# logic384.net
KiCad netlist of a schematic drawn in EAGLE
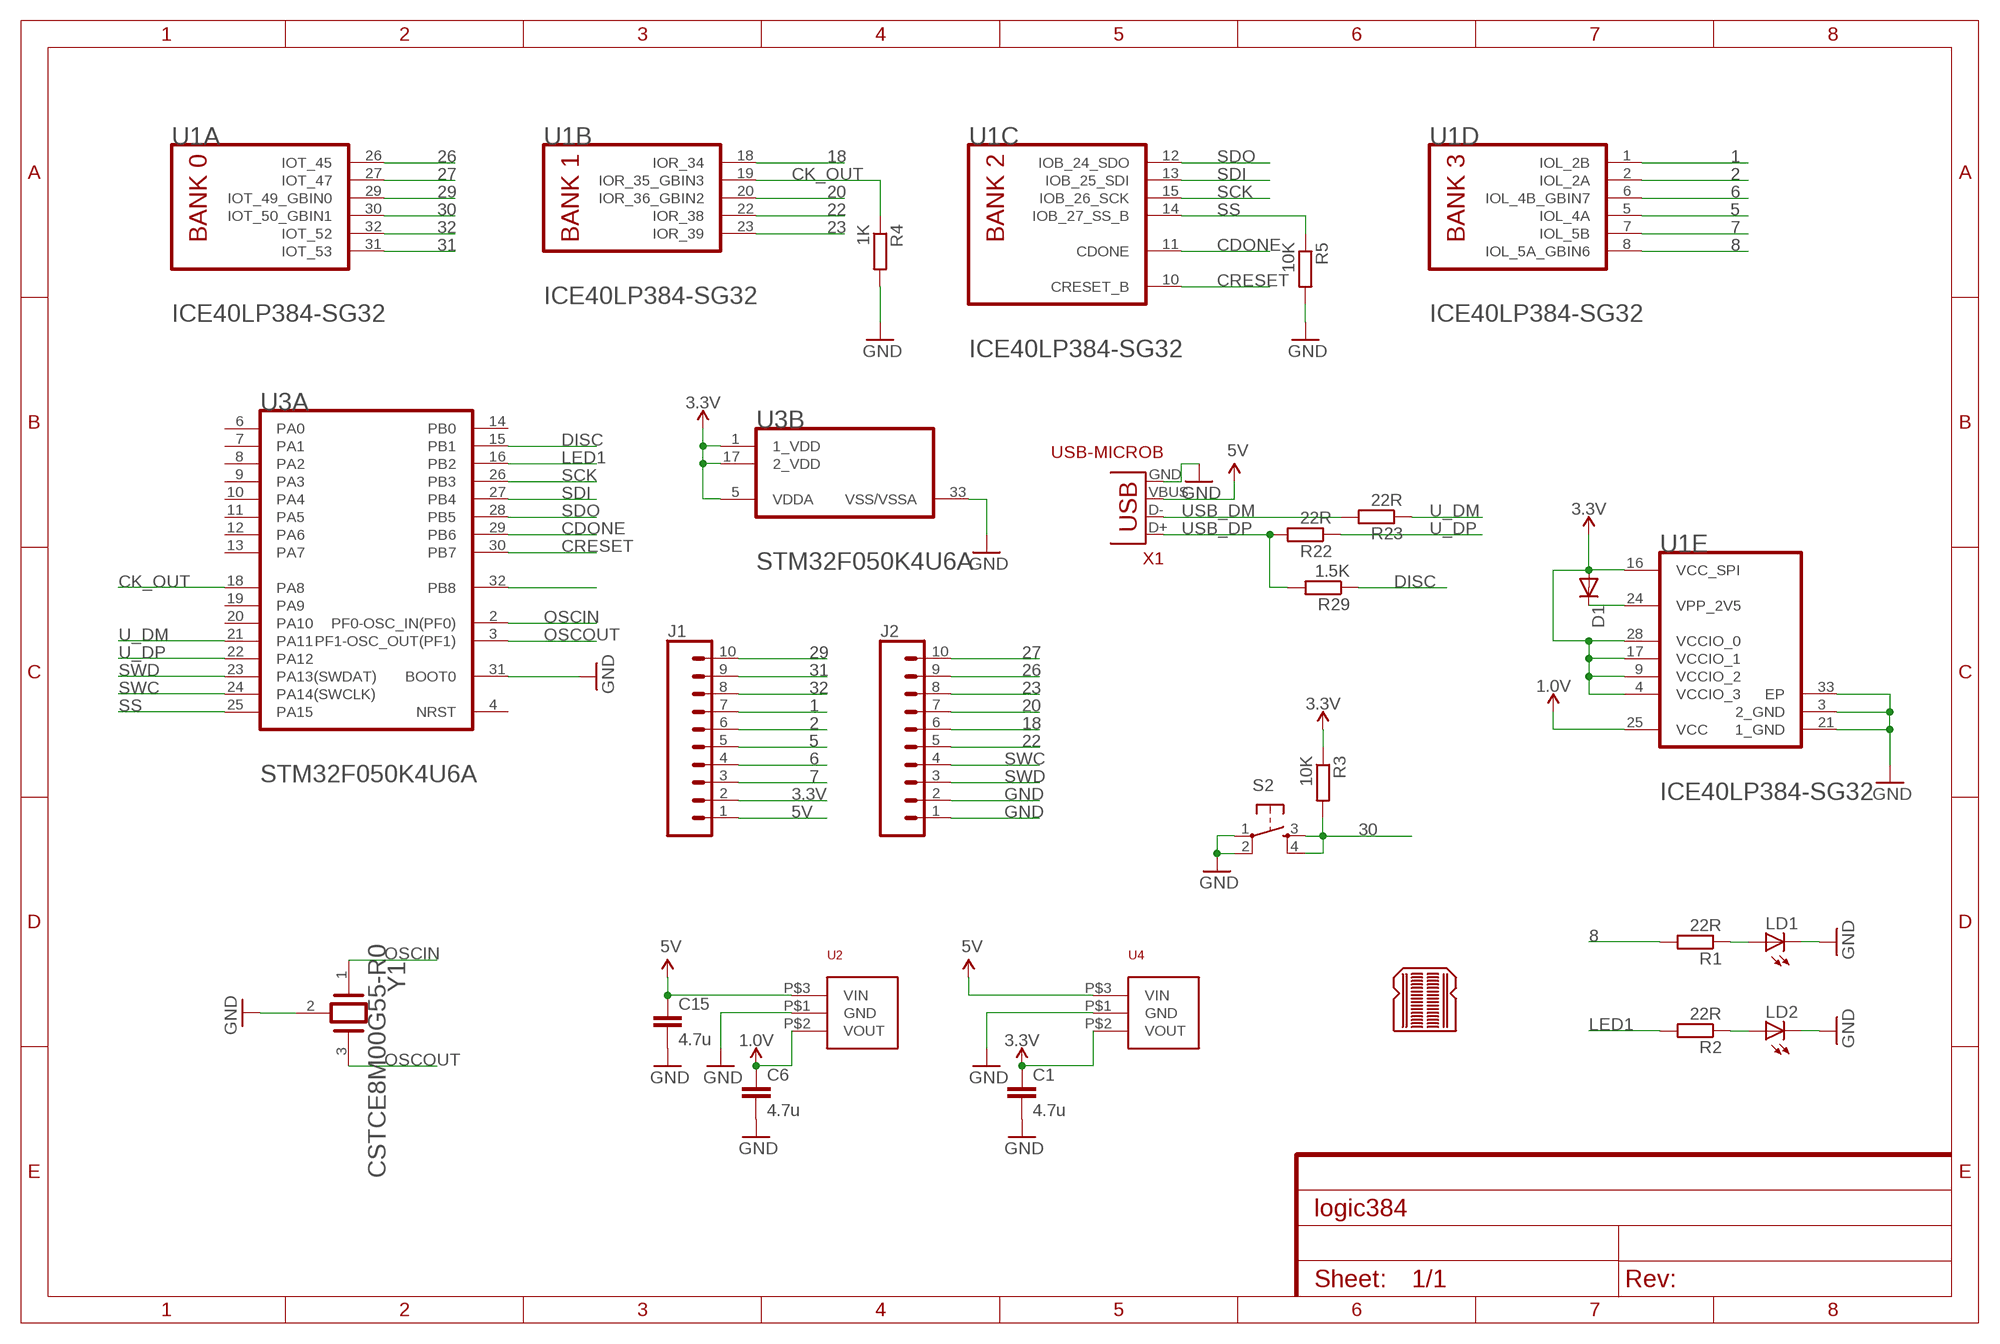
[diagram p0: schematic, sheet 1]

(export (version "E")
  (design (tool "Eeschema 10.0.6"))
  (components
    (comp (ref "C1")
      (value "4.7u")
      (footprint "eagle-import:0402-CAP")
      (libsource (lib "eagle-import") (part "CAP0402-CAP"))
    )
    (comp (ref "C6")
      (value "4.7u")
      (footprint "eagle-import:0402-CAP")
      (libsource (lib "eagle-import") (part "CAP0402-CAP"))
    )
    (comp (ref "C15")
      (value "4.7u")
      (footprint "eagle-import:0402-CAP")
      (libsource (lib "eagle-import") (part "CAP0402-CAP"))
    )
    (comp (ref "D1")
      (value "DIODE-SOD523")
      (footprint "eagle-import:SOD523")
      (libsource (lib "eagle-import") (part "DIODE-SOD523"))
    )
    (comp (ref "J1")
      (value "CONN_10NO_SILK_PTH_FEMALE")
      (footprint "eagle-import:1X10_NO_SILK")
      (libsource (lib "eagle-import") (part "CONN_10NO_SILK_PTH_FEMALE"))
    )
    (comp (ref "J2")
      (value "CONN_10NO_SILK_PTH_FEMALE")
      (footprint "eagle-import:1X10_NO_SILK")
      (libsource (lib "eagle-import") (part "CONN_10NO_SILK_PTH_FEMALE"))
    )
    (comp (ref "LD1")
      (value "LED0603")
      (footprint "eagle-import:LED-0603")
      (libsource (lib "eagle-import") (part "LED0603"))
    )
    (comp (ref "LD2")
      (value "LED0603")
      (footprint "eagle-import:LED-0603")
      (libsource (lib "eagle-import") (part "LED0603"))
    )
    (comp (ref "LOGO1")
      (value "BREADBOARD_PATTERN")
      (footprint "eagle-import:BREADBOARD_SPACING")
      (libsource (lib "eagle-import") (part "BREADBOARD_PATTERN"))
    )
    (comp (ref "R1")
      (value "22R")
      (footprint "eagle-import:R0402")
      (libsource (lib "eagle-import") (part "R-EU_R0402"))
    )
    (comp (ref "R2")
      (value "22R")
      (footprint "eagle-import:R0402")
      (libsource (lib "eagle-import") (part "R-EU_R0402"))
    )
    (comp (ref "R3")
      (value "10K")
      (footprint "eagle-import:R0402")
      (libsource (lib "eagle-import") (part "R-EU_R0402"))
    )
    (comp (ref "R4")
      (value "1K")
      (footprint "eagle-import:R0402")
      (libsource (lib "eagle-import") (part "R-EU_R0402"))
    )
    (comp (ref "R5")
      (value "10K")
      (footprint "eagle-import:R0402")
      (libsource (lib "eagle-import") (part "R-EU_R0402"))
    )
    (comp (ref "R22")
      (value "22R")
      (footprint "eagle-import:R0402")
      (libsource (lib "eagle-import") (part "R-EU_R0402"))
    )
    (comp (ref "R23")
      (value "22R")
      (footprint "eagle-import:R0402")
      (libsource (lib "eagle-import") (part "R-EU_R0402"))
    )
    (comp (ref "R29")
      (value "1.5K")
      (footprint "eagle-import:R0402")
      (libsource (lib "eagle-import") (part "R-EU_R0402"))
    )
    (comp (ref "S2")
      (value "TAC_SWITCHSMD")
      (footprint "eagle-import:TACTILE_SWITCH_SMD")
      (libsource (lib "eagle-import") (part "TAC_SWITCHSMD"))
    )
    (comp (ref "U1")
      (value "LATTICE_SEMICONDUCTOR_ICE40LP384-SG32LATTICE_SEMICONDUCTOR_ICE40LP384-SG32_0_1")
      (footprint "eagle-import:LATTICE_SEMICONDUCTOR_ICE40LP384-SG32_1")
      (fields (field (name "MF") "Lattice Semiconductor") (field (name "MPN") "ICE40LP384-SG32"))
      (libsource (lib "eagle-import") (part "LATTICE_SEMICONDUCTOR_ICE40LP384-SG32LATTICE_SEMICONDUCTOR_ICE40LP384-SG32_0_1"))
    )
    (comp (ref "U2")
      (value "MCP1703SOT-3.3V")
      (footprint "eagle-import:SOT-23A")
      (libsource (lib "eagle-import") (part "MCP1703SOT"))
    )
    (comp (ref "U3")
      (value "STMICROELECTRONICS_STM32F050K4U6ASTMICROELECTRONICS_STM32F050K4U6A_0_1")
      (footprint "eagle-import:STMICROELECTRONICS_STM32F050K4U6A_1")
      (fields (field (name "MF") "STMicroelectronics") (field (name "MPN") "STM32F050K4U6A"))
      (libsource (lib "eagle-import") (part "STMICROELECTRONICS_STM32F050K4U6ASTMICROELECTRONICS_STM32F050K4U6A_0_1"))
    )
    (comp (ref "U4")
      (value "MCP1703SOT-3.3V")
      (footprint "eagle-import:SOT-23A")
      (libsource (lib "eagle-import") (part "MCP1703SOT"))
    )
    (comp (ref "X1")
      (value "USB-MICROB")
      (footprint "eagle-import:USB-MICROB")
      (libsource (lib "eagle-import") (part "USB-MICROB"))
    )
    (comp (ref "Y1")
      (value "MURATA_CSTCE8M00G55-R0MURATA_CSTCE8M00G55-R0_0_0")
      (footprint "eagle-import:MURATA_CSTCE8M00G55-R0_0")
      (fields
        (field (name "DIGIKEY_PART_NUMBER") "490-1195-1-ND")
        (field (name "MF") "Murata")
        (field (name "MOUSER_PART_NUMBER") "81-CSTCE8M00G55-R0")
      )
      (libsource (lib "eagle-import") (part "MURATA_CSTCE8M00G55-R0MURATA_CSTCE8M00G55-R0_0_0"))
    )
  )
  (nets
    (net (code "1") (name "/1") (class "Default")
      (node (ref "J1") (pin "7") (pinfunction "7_7") (pintype "passive"))
      (node (ref "U1") (pin "1") (pinfunction "IOL_2B_1") (pintype "bidirectional"))
    )
    (net (code "2") (name "/2") (class "Default")
      (node (ref "J1") (pin "6") (pinfunction "6_6") (pintype "passive"))
      (node (ref "U1") (pin "2") (pinfunction "IOL_2A_2") (pintype "bidirectional"))
    )
    (net (code "3") (name "/5") (class "Default")
      (node (ref "J1") (pin "5") (pinfunction "5_5") (pintype "passive"))
      (node (ref "U1") (pin "5") (pinfunction "IOL_4A_5") (pintype "bidirectional"))
    )
    (net (code "4") (name "/6") (class "Default")
      (node (ref "J1") (pin "4") (pinfunction "4_4") (pintype "passive"))
      (node (ref "U1") (pin "6") (pinfunction "IOL_4B_GBIN7_6") (pintype "bidirectional"))
    )
    (net (code "5") (name "/7") (class "Default")
      (node (ref "J1") (pin "3") (pinfunction "3_3") (pintype "passive"))
      (node (ref "U1") (pin "7") (pinfunction "IOL_5B_7") (pintype "bidirectional"))
    )
    (net (code "6") (name "/8") (class "Default")
      (node (ref "R1") (pin "2") (pinfunction "2_2") (pintype "passive"))
      (node (ref "U1") (pin "8") (pinfunction "IOL_5A_GBIN6_8") (pintype "bidirectional"))
    )
    (net (code "7") (name "/18") (class "Default")
      (node (ref "J2") (pin "6") (pinfunction "6_6") (pintype "passive"))
      (node (ref "U1") (pin "18") (pinfunction "IOR_34_18") (pintype "bidirectional"))
    )
    (net (code "8") (name "/20") (class "Default")
      (node (ref "J2") (pin "7") (pinfunction "7_7") (pintype "passive"))
      (node (ref "U1") (pin "20") (pinfunction "IOR_36_GBIN2_20") (pintype "bidirectional"))
    )
    (net (code "9") (name "/22") (class "Default")
      (node (ref "J2") (pin "5") (pinfunction "5_5") (pintype "passive"))
      (node (ref "U1") (pin "22") (pinfunction "IOR_38_22") (pintype "bidirectional"))
    )
    (net (code "10") (name "/23") (class "Default")
      (node (ref "J2") (pin "8") (pinfunction "8_8") (pintype "passive"))
      (node (ref "U1") (pin "23") (pinfunction "IOR_39_23") (pintype "bidirectional"))
    )
    (net (code "11") (name "/26") (class "Default")
      (node (ref "J2") (pin "9") (pinfunction "9_9") (pintype "passive"))
      (node (ref "U1") (pin "26") (pinfunction "IOT_45_26") (pintype "bidirectional"))
    )
    (net (code "12") (name "/27") (class "Default")
      (node (ref "J2") (pin "10") (pinfunction "10_10") (pintype "passive"))
      (node (ref "U1") (pin "27") (pinfunction "IOT_47_27") (pintype "bidirectional"))
    )
    (net (code "13") (name "/29") (class "Default")
      (node (ref "J1") (pin "10") (pinfunction "10_10") (pintype "passive"))
      (node (ref "U1") (pin "29") (pinfunction "IOT_49_GBIN0_29") (pintype "bidirectional"))
    )
    (net (code "14") (name "/30") (class "Default")
      (node (ref "R3") (pin "2") (pinfunction "2_2") (pintype "passive"))
      (node (ref "S2") (pin "3") (pinfunction "3_3") (pintype "passive"))
      (node (ref "S2") (pin "4") (pinfunction "4_4") (pintype "passive"))
      (node (ref "U1") (pin "30") (pinfunction "IOT_50_GBIN1_30") (pintype "bidirectional"))
    )
    (net (code "15") (name "/31") (class "Default")
      (node (ref "J1") (pin "9") (pinfunction "9_9") (pintype "passive"))
      (node (ref "U1") (pin "31") (pinfunction "IOT_53_31") (pintype "bidirectional"))
    )
    (net (code "16") (name "/32") (class "Default")
      (node (ref "J1") (pin "8") (pinfunction "8_8") (pintype "passive"))
      (node (ref "U1") (pin "32") (pinfunction "IOT_52_32") (pintype "bidirectional"))
    )
    (net (code "17") (name "/CDONE") (class "Default")
      (node (ref "U1") (pin "11") (pinfunction "CDONE_11") (pintype "bidirectional"))
      (node (ref "U3") (pin "29") (pinfunction "PB6_29") (pintype "bidirectional"))
    )
    (net (code "18") (name "/CK_OUT") (class "Default")
      (node (ref "R4") (pin "1") (pinfunction "1_1") (pintype "passive"))
      (node (ref "U1") (pin "19") (pinfunction "IOR_35_GBIN3_19") (pintype "bidirectional"))
      (node (ref "U3") (pin "18") (pinfunction "PA8_18") (pintype "bidirectional"))
    )
    (net (code "19") (name "/CRESET") (class "Default")
      (node (ref "U1") (pin "10") (pinfunction "CRESET_B_10") (pintype "input"))
      (node (ref "U3") (pin "30") (pinfunction "PB7_30") (pintype "bidirectional"))
    )
    (net (code "20") (name "/DISC") (class "Default")
      (node (ref "R29") (pin "1") (pinfunction "1_1") (pintype "passive"))
      (node (ref "U3") (pin "15") (pinfunction "PB1_15") (pintype "bidirectional"))
    )
    (net (code "21") (name "/LED1") (class "Default")
      (node (ref "R2") (pin "2") (pinfunction "2_2") (pintype "passive"))
      (node (ref "U3") (pin "16") (pinfunction "PB2_16") (pintype "bidirectional"))
    )
    (net (code "22") (name "/OSCIN") (class "Default")
      (node (ref "U3") (pin "2") (pinfunction "PF0-OSC_IN(PF0)_2") (pintype "bidirectional"))
      (node (ref "Y1") (pin "1") (pinfunction "1_1") (pintype "bidirectional"))
    )
    (net (code "23") (name "/OSCOUT") (class "Default")
      (node (ref "U3") (pin "3") (pinfunction "PF1-OSC_OUT(PF1)_3") (pintype "bidirectional"))
      (node (ref "Y1") (pin "3") (pinfunction "3_3") (pintype "bidirectional"))
    )
    (net (code "24") (name "/SCK") (class "Default")
      (node (ref "U1") (pin "15") (pinfunction "IOB_26_SCK_15") (pintype "bidirectional"))
      (node (ref "U3") (pin "26") (pinfunction "PB3_26") (pintype "bidirectional"))
    )
    (net (code "25") (name "/SDI") (class "Default")
      (node (ref "U1") (pin "13") (pinfunction "IOB_25_SDI_13") (pintype "bidirectional"))
      (node (ref "U3") (pin "27") (pinfunction "PB4_27") (pintype "bidirectional"))
    )
    (net (code "26") (name "/SDO") (class "Default")
      (node (ref "U1") (pin "12") (pinfunction "IOB_24_SDO_12") (pintype "bidirectional"))
      (node (ref "U3") (pin "28") (pinfunction "PB5_28") (pintype "bidirectional"))
    )
    (net (code "27") (name "/SS") (class "Default")
      (node (ref "R5") (pin "1") (pinfunction "1_1") (pintype "passive"))
      (node (ref "U1") (pin "14") (pinfunction "IOB_27_SS_B_14") (pintype "bidirectional"))
      (node (ref "U3") (pin "25") (pinfunction "PA15_25") (pintype "bidirectional"))
    )
    (net (code "28") (name "/SWC") (class "Default")
      (node (ref "J2") (pin "4") (pinfunction "4_4") (pintype "passive"))
      (node (ref "U3") (pin "24") (pinfunction "PA14(SWCLK)_24") (pintype "bidirectional"))
    )
    (net (code "29") (name "/SWD") (class "Default")
      (node (ref "J2") (pin "3") (pinfunction "3_3") (pintype "passive"))
      (node (ref "U3") (pin "23") (pinfunction "PA13(SWDAT)_23") (pintype "bidirectional"))
    )
    (net (code "30") (name "/USB_DM") (class "Default")
      (node (ref "R23") (pin "2") (pinfunction "2_2") (pintype "passive"))
      (node (ref "X1") (pin "D-") (pinfunction "D-_D-") (pintype "bidirectional"))
    )
    (net (code "31") (name "/USB_DP") (class "Default")
      (node (ref "R22") (pin "2") (pinfunction "2_2") (pintype "passive"))
      (node (ref "R29") (pin "2") (pinfunction "2_2") (pintype "passive"))
      (node (ref "X1") (pin "D+") (pinfunction "D+_D+") (pintype "bidirectional"))
    )
    (net (code "32") (name "/U_DM") (class "Default")
      (node (ref "R23") (pin "1") (pinfunction "1_1") (pintype "passive"))
      (node (ref "U3") (pin "21") (pinfunction "PA11_21") (pintype "bidirectional"))
    )
    (net (code "33") (name "/U_DP") (class "Default")
      (node (ref "R22") (pin "1") (pinfunction "1_1") (pintype "passive"))
      (node (ref "U3") (pin "22") (pinfunction "PA12_22") (pintype "bidirectional"))
    )
    (net (code "34") (name "1.0V") (class "Default")
      (node (ref "C6") (pin "1") (pinfunction "1_1") (pintype "passive"))
      (node (ref "U1") (pin "25") (pinfunction "VCC_25") (pintype "power_in"))
      (node (ref "U2") (pin "P$2") (pinfunction "VOUT_P$2") (pintype "bidirectional"))
    )
    (net (code "35") (name "3.3V") (class "Default")
      (node (ref "C1") (pin "1") (pinfunction "1_1") (pintype "passive"))
      (node (ref "D1") (pin "A") (pinfunction "A_A") (pintype "passive"))
      (node (ref "J1") (pin "2") (pinfunction "2_2") (pintype "passive"))
      (node (ref "R3") (pin "1") (pinfunction "1_1") (pintype "passive"))
      (node (ref "U1") (pin "16") (pinfunction "VCC_SPI_16") (pintype "power_in"))
      (node (ref "U1") (pin "17") (pinfunction "VCCIO_1_17") (pintype "power_in"))
      (node (ref "U1") (pin "28") (pinfunction "VCCIO_0_28") (pintype "power_in"))
      (node (ref "U1") (pin "4") (pinfunction "VCCIO_3_4") (pintype "power_in"))
      (node (ref "U1") (pin "9") (pinfunction "VCCIO_2_9") (pintype "power_in"))
      (node (ref "U3") (pin "1") (pinfunction "1_VDD_1") (pintype "power_in"))
      (node (ref "U3") (pin "17") (pinfunction "2_VDD_17") (pintype "power_in"))
      (node (ref "U3") (pin "5") (pinfunction "VDDA_5") (pintype "power_in"))
      (node (ref "U4") (pin "P$2") (pinfunction "VOUT_P$2") (pintype "bidirectional"))
    )
    (net (code "36") (name "5V") (class "Default")
      (node (ref "C15") (pin "1") (pinfunction "1_1") (pintype "passive"))
      (node (ref "J1") (pin "1") (pinfunction "1_1") (pintype "passive"))
      (node (ref "U2") (pin "P$3") (pinfunction "VIN_P$3") (pintype "bidirectional"))
      (node (ref "U4") (pin "P$3") (pinfunction "VIN_P$3") (pintype "bidirectional"))
      (node (ref "X1") (pin "VBUS") (pinfunction "VBUS_VBUS") (pintype "bidirectional"))
    )
    (net (code "37") (name "GND") (class "Default")
      (node (ref "C1") (pin "2") (pinfunction "2_2") (pintype "passive"))
      (node (ref "C15") (pin "2") (pinfunction "2_2") (pintype "passive"))
      (node (ref "C6") (pin "2") (pinfunction "2_2") (pintype "passive"))
      (node (ref "J2") (pin "1") (pinfunction "1_1") (pintype "passive"))
      (node (ref "J2") (pin "2") (pinfunction "2_2") (pintype "passive"))
      (node (ref "LD1") (pin "C") (pinfunction "C_C") (pintype "passive"))
      (node (ref "LD2") (pin "C") (pinfunction "C_C") (pintype "passive"))
      (node (ref "R4") (pin "2") (pinfunction "2_2") (pintype "passive"))
      (node (ref "R5") (pin "2") (pinfunction "2_2") (pintype "passive"))
      (node (ref "S2") (pin "1") (pinfunction "1_1") (pintype "passive"))
      (node (ref "S2") (pin "2") (pinfunction "2_2") (pintype "passive"))
      (node (ref "U1") (pin "21") (pinfunction "1_GND_21") (pintype "power_in"))
      (node (ref "U1") (pin "3") (pinfunction "2_GND_3") (pintype "power_in"))
      (node (ref "U1") (pin "33") (pinfunction "EP_33") (pintype "passive"))
      (node (ref "U2") (pin "P$1") (pinfunction "GND_P$1") (pintype "bidirectional"))
      (node (ref "U3") (pin "31") (pinfunction "BOOT0_31") (pintype "input"))
      (node (ref "U3") (pin "33") (pinfunction "VSS/VSSA_33") (pintype "power_in"))
      (node (ref "U4") (pin "P$1") (pinfunction "GND_P$1") (pintype "bidirectional"))
      (node (ref "X1") (pin "GND") (pinfunction "GND_GND") (pintype "bidirectional"))
      (node (ref "Y1") (pin "2") (pinfunction "2_2") (pintype "bidirectional"))
    )
    (net (code "38") (name "Net-(LD1-PadA)") (class "Default")
      (node (ref "LD1") (pin "A") (pinfunction "A_A") (pintype "passive"))
      (node (ref "R1") (pin "1") (pinfunction "1_1") (pintype "passive"))
    )
    (net (code "39") (name "Net-(LD2-PadA)") (class "Default")
      (node (ref "LD2") (pin "A") (pinfunction "A_A") (pintype "passive"))
      (node (ref "R2") (pin "1") (pinfunction "1_1") (pintype "passive"))
    )
    (net (code "40") (name "Net-(U1E-VPP_2V5)") (class "Default")
      (node (ref "D1") (pin "C") (pinfunction "C_C") (pintype "passive"))
      (node (ref "U1") (pin "24") (pinfunction "VPP_2V5_24") (pintype "power_in"))
    )
    (net (code "41") (name "unconnected-(U3A-NRST-Pad4)") (class "Default")
      (node (ref "U3") (pin "4") (pinfunction "NRST_4") (pintype "bidirectional"))
    )
    (net (code "42") (name "unconnected-(U3A-PA0-Pad6)") (class "Default")
      (node (ref "U3") (pin "6") (pinfunction "PA0_6") (pintype "bidirectional"))
    )
    (net (code "43") (name "unconnected-(U3A-PA1-Pad7)") (class "Default")
      (node (ref "U3") (pin "7") (pinfunction "PA1_7") (pintype "bidirectional"))
    )
    (net (code "44") (name "unconnected-(U3A-PA2-Pad8)") (class "Default")
      (node (ref "U3") (pin "8") (pinfunction "PA2_8") (pintype "bidirectional"))
    )
    (net (code "45") (name "unconnected-(U3A-PA3-Pad9)") (class "Default")
      (node (ref "U3") (pin "9") (pinfunction "PA3_9") (pintype "bidirectional"))
    )
    (net (code "46") (name "unconnected-(U3A-PA4-Pad10)") (class "Default")
      (node (ref "U3") (pin "10") (pinfunction "PA4_10") (pintype "bidirectional"))
    )
    (net (code "47") (name "unconnected-(U3A-PA5-Pad11)") (class "Default")
      (node (ref "U3") (pin "11") (pinfunction "PA5_11") (pintype "bidirectional"))
    )
    (net (code "48") (name "unconnected-(U3A-PA6-Pad12)") (class "Default")
      (node (ref "U3") (pin "12") (pinfunction "PA6_12") (pintype "bidirectional"))
    )
    (net (code "49") (name "unconnected-(U3A-PA7-Pad13)") (class "Default")
      (node (ref "U3") (pin "13") (pinfunction "PA7_13") (pintype "bidirectional"))
    )
    (net (code "50") (name "unconnected-(U3A-PA9-Pad19)") (class "Default")
      (node (ref "U3") (pin "19") (pinfunction "PA9_19") (pintype "bidirectional"))
    )
    (net (code "51") (name "unconnected-(U3A-PA10-Pad20)") (class "Default")
      (node (ref "U3") (pin "20") (pinfunction "PA10_20") (pintype "bidirectional"))
    )
    (net (code "52") (name "unconnected-(U3A-PB0-Pad14)") (class "Default")
      (node (ref "U3") (pin "14") (pinfunction "PB0_14") (pintype "bidirectional"))
    )
    (net (code "53") (name "unconnected-(U3A-PB8-Pad32)") (class "Default")
      (node (ref "U3") (pin "32") (pinfunction "PB8_32") (pintype "bidirectional"))
    )
  )
)
